# connector.net
KiCad netlist of a schematic drawn in Altium Designer
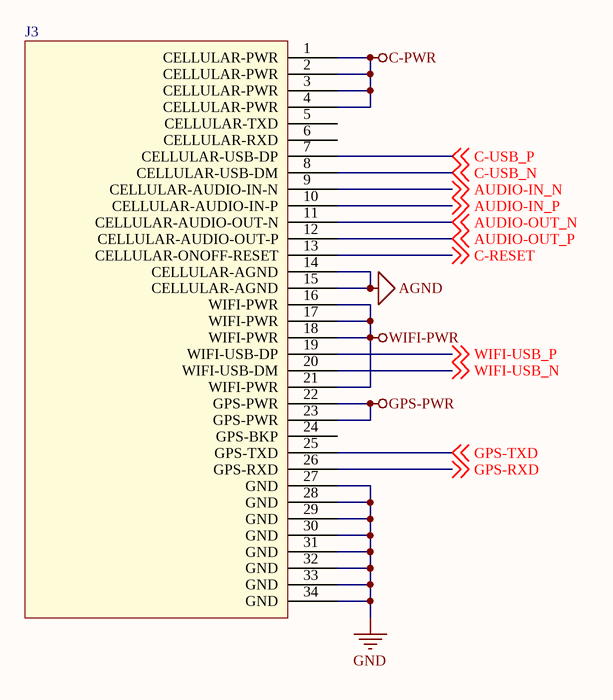
[diagram p0: connector.SchDoc]

(export (version "E")
  (design (tool "Eeschema 10.0.6"))
  (components
    (comp (ref "J3")
      (value "COMM_BOARD")
      (footprint "HEAD_2MM_2X17")
      (libsource (lib "Schlib") (part "COMM_BOARD"))
    )
  )
  (nets
    (net (code "1") (name "AGND") (class "Default")
      (node (ref "J3") (pin "14") (pinfunction "CELLULAR-AGND_14") (pintype "passive"))
      (node (ref "J3") (pin "15") (pinfunction "CELLULAR-AGND_15") (pintype "passive"))
    )
    (net (code "2") (name "AUDIO-IN_N") (class "Default")
      (node (ref "J3") (pin "9") (pinfunction "CELLULAR-AUDIO-IN-N_9") (pintype "passive"))
    )
    (net (code "3") (name "AUDIO-IN_P") (class "Default")
      (node (ref "J3") (pin "10") (pinfunction "CELLULAR-AUDIO-IN-P_10") (pintype "passive"))
    )
    (net (code "4") (name "AUDIO-OUT_N") (class "Default")
      (node (ref "J3") (pin "11") (pinfunction "CELLULAR-AUDIO-OUT-N_11") (pintype "passive"))
    )
    (net (code "5") (name "AUDIO-OUT_P") (class "Default")
      (node (ref "J3") (pin "12") (pinfunction "CELLULAR-AUDIO-OUT-P_12") (pintype "passive"))
    )
    (net (code "6") (name "C-PWR") (class "Default")
      (node (ref "J3") (pin "1") (pinfunction "CELLULAR-PWR_1") (pintype "passive"))
      (node (ref "J3") (pin "2") (pinfunction "CELLULAR-PWR_2") (pintype "passive"))
      (node (ref "J3") (pin "3") (pinfunction "CELLULAR-PWR_3") (pintype "passive"))
      (node (ref "J3") (pin "4") (pinfunction "CELLULAR-PWR_4") (pintype "passive"))
    )
    (net (code "7") (name "C-RESET") (class "Default")
      (node (ref "J3") (pin "13") (pinfunction "CELLULAR-ONOFF-RESET_13") (pintype "passive"))
    )
    (net (code "8") (name "C-USB_N") (class "Default")
      (node (ref "J3") (pin "8") (pinfunction "CELLULAR-USB-DM_8") (pintype "passive"))
    )
    (net (code "9") (name "C-USB_P") (class "Default")
      (node (ref "J3") (pin "7") (pinfunction "CELLULAR-USB-DP_7") (pintype "passive"))
    )
    (net (code "10") (name "GND") (class "Default")
      (node (ref "J3") (pin "27") (pinfunction "GND_27") (pintype "passive"))
      (node (ref "J3") (pin "28") (pinfunction "GND_28") (pintype "passive"))
      (node (ref "J3") (pin "29") (pinfunction "GND_29") (pintype "passive"))
      (node (ref "J3") (pin "30") (pinfunction "GND_30") (pintype "passive"))
      (node (ref "J3") (pin "31") (pinfunction "GND_31") (pintype "passive"))
      (node (ref "J3") (pin "32") (pinfunction "GND_32") (pintype "passive"))
      (node (ref "J3") (pin "33") (pinfunction "GND_33") (pintype "passive"))
      (node (ref "J3") (pin "34") (pinfunction "GND_34") (pintype "passive"))
    )
    (net (code "11") (name "GPS-PWR") (class "Default")
      (node (ref "J3") (pin "22") (pinfunction "GPS-PWR_22") (pintype "passive"))
      (node (ref "J3") (pin "23") (pinfunction "GPS-PWR_23") (pintype "passive"))
    )
    (net (code "12") (name "GPS-RXD") (class "Default")
      (node (ref "J3") (pin "26") (pinfunction "GPS-RXD_26") (pintype "passive"))
    )
    (net (code "13") (name "GPS-TXD") (class "Default")
      (node (ref "J3") (pin "25") (pinfunction "GPS-TXD_25") (pintype "passive"))
    )
    (net (code "14") (name "WIFI-PWR") (class "Default")
      (node (ref "J3") (pin "16") (pinfunction "WIFI-PWR_16") (pintype "passive"))
      (node (ref "J3") (pin "17") (pinfunction "WIFI-PWR_17") (pintype "passive"))
      (node (ref "J3") (pin "18") (pinfunction "WIFI-PWR_18") (pintype "passive"))
      (node (ref "J3") (pin "21") (pinfunction "WIFI-PWR_21") (pintype "passive"))
    )
    (net (code "15") (name "WIFI-USB_N") (class "Default")
      (node (ref "J3") (pin "20") (pinfunction "WIFI-USB-DM_20") (pintype "passive"))
    )
    (net (code "16") (name "WIFI-USB_P") (class "Default")
      (node (ref "J3") (pin "19") (pinfunction "WIFI-USB-DP_19") (pintype "passive"))
    )
    (net (code "17") (name "unconnected-(J3-CELLULAR-RXD-Pad6)") (class "Default")
      (node (ref "J3") (pin "6") (pinfunction "CELLULAR-RXD_6") (pintype "passive"))
    )
    (net (code "18") (name "unconnected-(J3-CELLULAR-TXD-Pad5)") (class "Default")
      (node (ref "J3") (pin "5") (pinfunction "CELLULAR-TXD_5") (pintype "passive"))
    )
    (net (code "19") (name "unconnected-(J3-GPS-BKP-Pad24)") (class "Default")
      (node (ref "J3") (pin "24") (pinfunction "GPS-BKP_24") (pintype "passive"))
    )
  )
)
